# MC14490P_module_PCB.net
KiCad netlist of a schematic drawn in Altium Designer
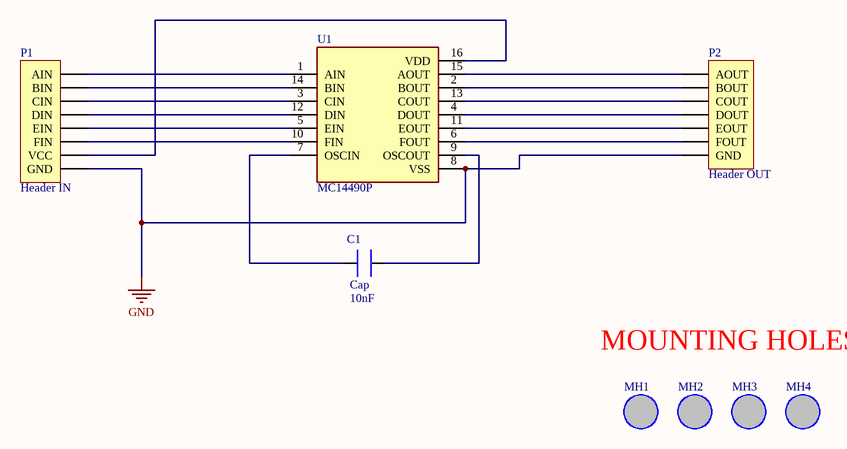
[diagram p0: MC14490P_module_PCB.SchDoc]

(export (version "E")
  (design (tool "Eeschema 10.0.6"))
  (components
    (comp (ref "C1")
      (value "Cap")
      (footprint "RAD-0.3")
      (description "Capacitor")
      (fields (field (name "ALTIUM_VALUE") "10nF") (field (name "PUBLISHER") "Altium Limited"))
      (libsource (lib "MC14490P") (part "Cap"))
    )
    (comp (ref "MH1")
      (value "Mounting Hole 3.2mm Drill")
      (footprint "MH_3.2MMD")
      (libsource (lib "Schlib1") (part "MH_3.2MMD"))
    )
    (comp (ref "MH2")
      (value "Mounting Hole 3.2mm Drill")
      (footprint "MH_3.2MMD")
      (libsource (lib "Schlib1") (part "MH_3.2MMD"))
    )
    (comp (ref "MH3")
      (value "Mounting Hole 3.2mm Drill")
      (footprint "MH_3.2MMD")
      (libsource (lib "Schlib1") (part "MH_3.2MMD"))
    )
    (comp (ref "MH4")
      (value "Mounting Hole 3.2mm Drill")
      (footprint "MH_3.2MMD")
      (libsource (lib "Schlib1") (part "MH_3.2MMD"))
    )
    (comp (ref "P1")
      (value "Header IN")
      (footprint "HDR1X8")
      (description "Header, 8-Pin debounce input")
      (fields (field (name "PUBLISHER") "Altium Limited"))
      (libsource (lib "MC14490P") (part "Header8_Debounce"))
    )
    (comp (ref "P2")
      (value "Header OUT")
      (footprint "HDR1X7")
      (description "Header, 7-Pin debounce output")
      (fields (field (name "PUBLISHER") "Altium Limited"))
      (libsource (lib "MC14490P") (part "Header_7_Debounce"))
    )
    (comp (ref "U1")
      (value "MC14490P")
      (footprint "DIP762W46P254L1918H444Q16P")
      (description "Contact Bounce Eliminator IC 16-DIP")
      (fields (field (name "MF") "ON Semiconductor"))
      (libsource (lib "MC14490P") (part "MC14490P"))
    )
  )
  (nets
    (net (code "1") (name "GND") (class "Default")
      (node (ref "P1") (pin "1") (pinfunction "GND_1") (pintype "passive"))
      (node (ref "P2") (pin "1") (pinfunction "GND_1") (pintype "passive"))
      (node (ref "U1") (pin "8") (pinfunction "VSS_8") (pintype "power_in"))
    )
    (net (code "2") (name "Net-(P1-AIN)") (class "Default")
      (node (ref "P1") (pin "8") (pinfunction "AIN_8") (pintype "passive"))
      (node (ref "U1") (pin "1") (pinfunction "AIN_1") (pintype "passive"))
    )
    (net (code "3") (name "Net-(P1-BIN)") (class "Default")
      (node (ref "P1") (pin "7") (pinfunction "BIN_7") (pintype "passive"))
      (node (ref "U1") (pin "14") (pinfunction "BIN_14") (pintype "passive"))
    )
    (net (code "4") (name "Net-(P1-CIN)") (class "Default")
      (node (ref "P1") (pin "6") (pinfunction "CIN_6") (pintype "passive"))
      (node (ref "U1") (pin "3") (pinfunction "CIN_3") (pintype "passive"))
    )
    (net (code "5") (name "Net-(P1-DIN)") (class "Default")
      (node (ref "P1") (pin "5") (pinfunction "DIN_5") (pintype "passive"))
      (node (ref "U1") (pin "12") (pinfunction "DIN_12") (pintype "passive"))
    )
    (net (code "6") (name "Net-(P1-EIN)") (class "Default")
      (node (ref "P1") (pin "4") (pinfunction "EIN_4") (pintype "passive"))
      (node (ref "U1") (pin "5") (pinfunction "EIN_5") (pintype "passive"))
    )
    (net (code "7") (name "Net-(P1-FIN)") (class "Default")
      (node (ref "P1") (pin "3") (pinfunction "FIN_3") (pintype "passive"))
      (node (ref "U1") (pin "10") (pinfunction "FIN_10") (pintype "passive"))
    )
    (net (code "8") (name "Net-(P1-VCC)") (class "Default")
      (node (ref "P1") (pin "2") (pinfunction "VCC_2") (pintype "passive"))
      (node (ref "U1") (pin "16") (pinfunction "VDD_16") (pintype "power_in"))
    )
    (net (code "9") (name "Net-(P2-AOUT)") (class "Default")
      (node (ref "P2") (pin "7") (pinfunction "AOUT_7") (pintype "passive"))
      (node (ref "U1") (pin "15") (pinfunction "AOUT_15") (pintype "passive"))
    )
    (net (code "10") (name "Net-(P2-BOUT)") (class "Default")
      (node (ref "P2") (pin "6") (pinfunction "BOUT_6") (pintype "passive"))
      (node (ref "U1") (pin "2") (pinfunction "BOUT_2") (pintype "passive"))
    )
    (net (code "11") (name "Net-(P2-COUT)") (class "Default")
      (node (ref "P2") (pin "5") (pinfunction "COUT_5") (pintype "passive"))
      (node (ref "U1") (pin "13") (pinfunction "COUT_13") (pintype "passive"))
    )
    (net (code "12") (name "Net-(P2-DOUT)") (class "Default")
      (node (ref "P2") (pin "4") (pinfunction "DOUT_4") (pintype "passive"))
      (node (ref "U1") (pin "4") (pinfunction "DOUT_4") (pintype "passive"))
    )
    (net (code "13") (name "Net-(P2-EOUT)") (class "Default")
      (node (ref "P2") (pin "3") (pinfunction "EOUT_3") (pintype "passive"))
      (node (ref "U1") (pin "11") (pinfunction "EOUT_11") (pintype "passive"))
    )
    (net (code "14") (name "Net-(P2-FOUT)") (class "Default")
      (node (ref "P2") (pin "2") (pinfunction "FOUT_2") (pintype "passive"))
      (node (ref "U1") (pin "6") (pinfunction "FOUT_6") (pintype "passive"))
    )
    (net (code "15") (name "Net-(U1-OSCIN)") (class "Default")
      (node (ref "C1") (pin "1") (pinfunction "1_1") (pintype "passive"))
      (node (ref "U1") (pin "7") (pinfunction "OSCIN_7") (pintype "passive"))
    )
    (net (code "16") (name "Net-(U1-OSCOUT)") (class "Default")
      (node (ref "C1") (pin "2") (pinfunction "2_2") (pintype "passive"))
      (node (ref "U1") (pin "9") (pinfunction "OSCOUT_9") (pintype "passive"))
    )
  )
)
